# Brushed_Motor_MCU.net
KiCad netlist of a schematic drawn in Altium Designer
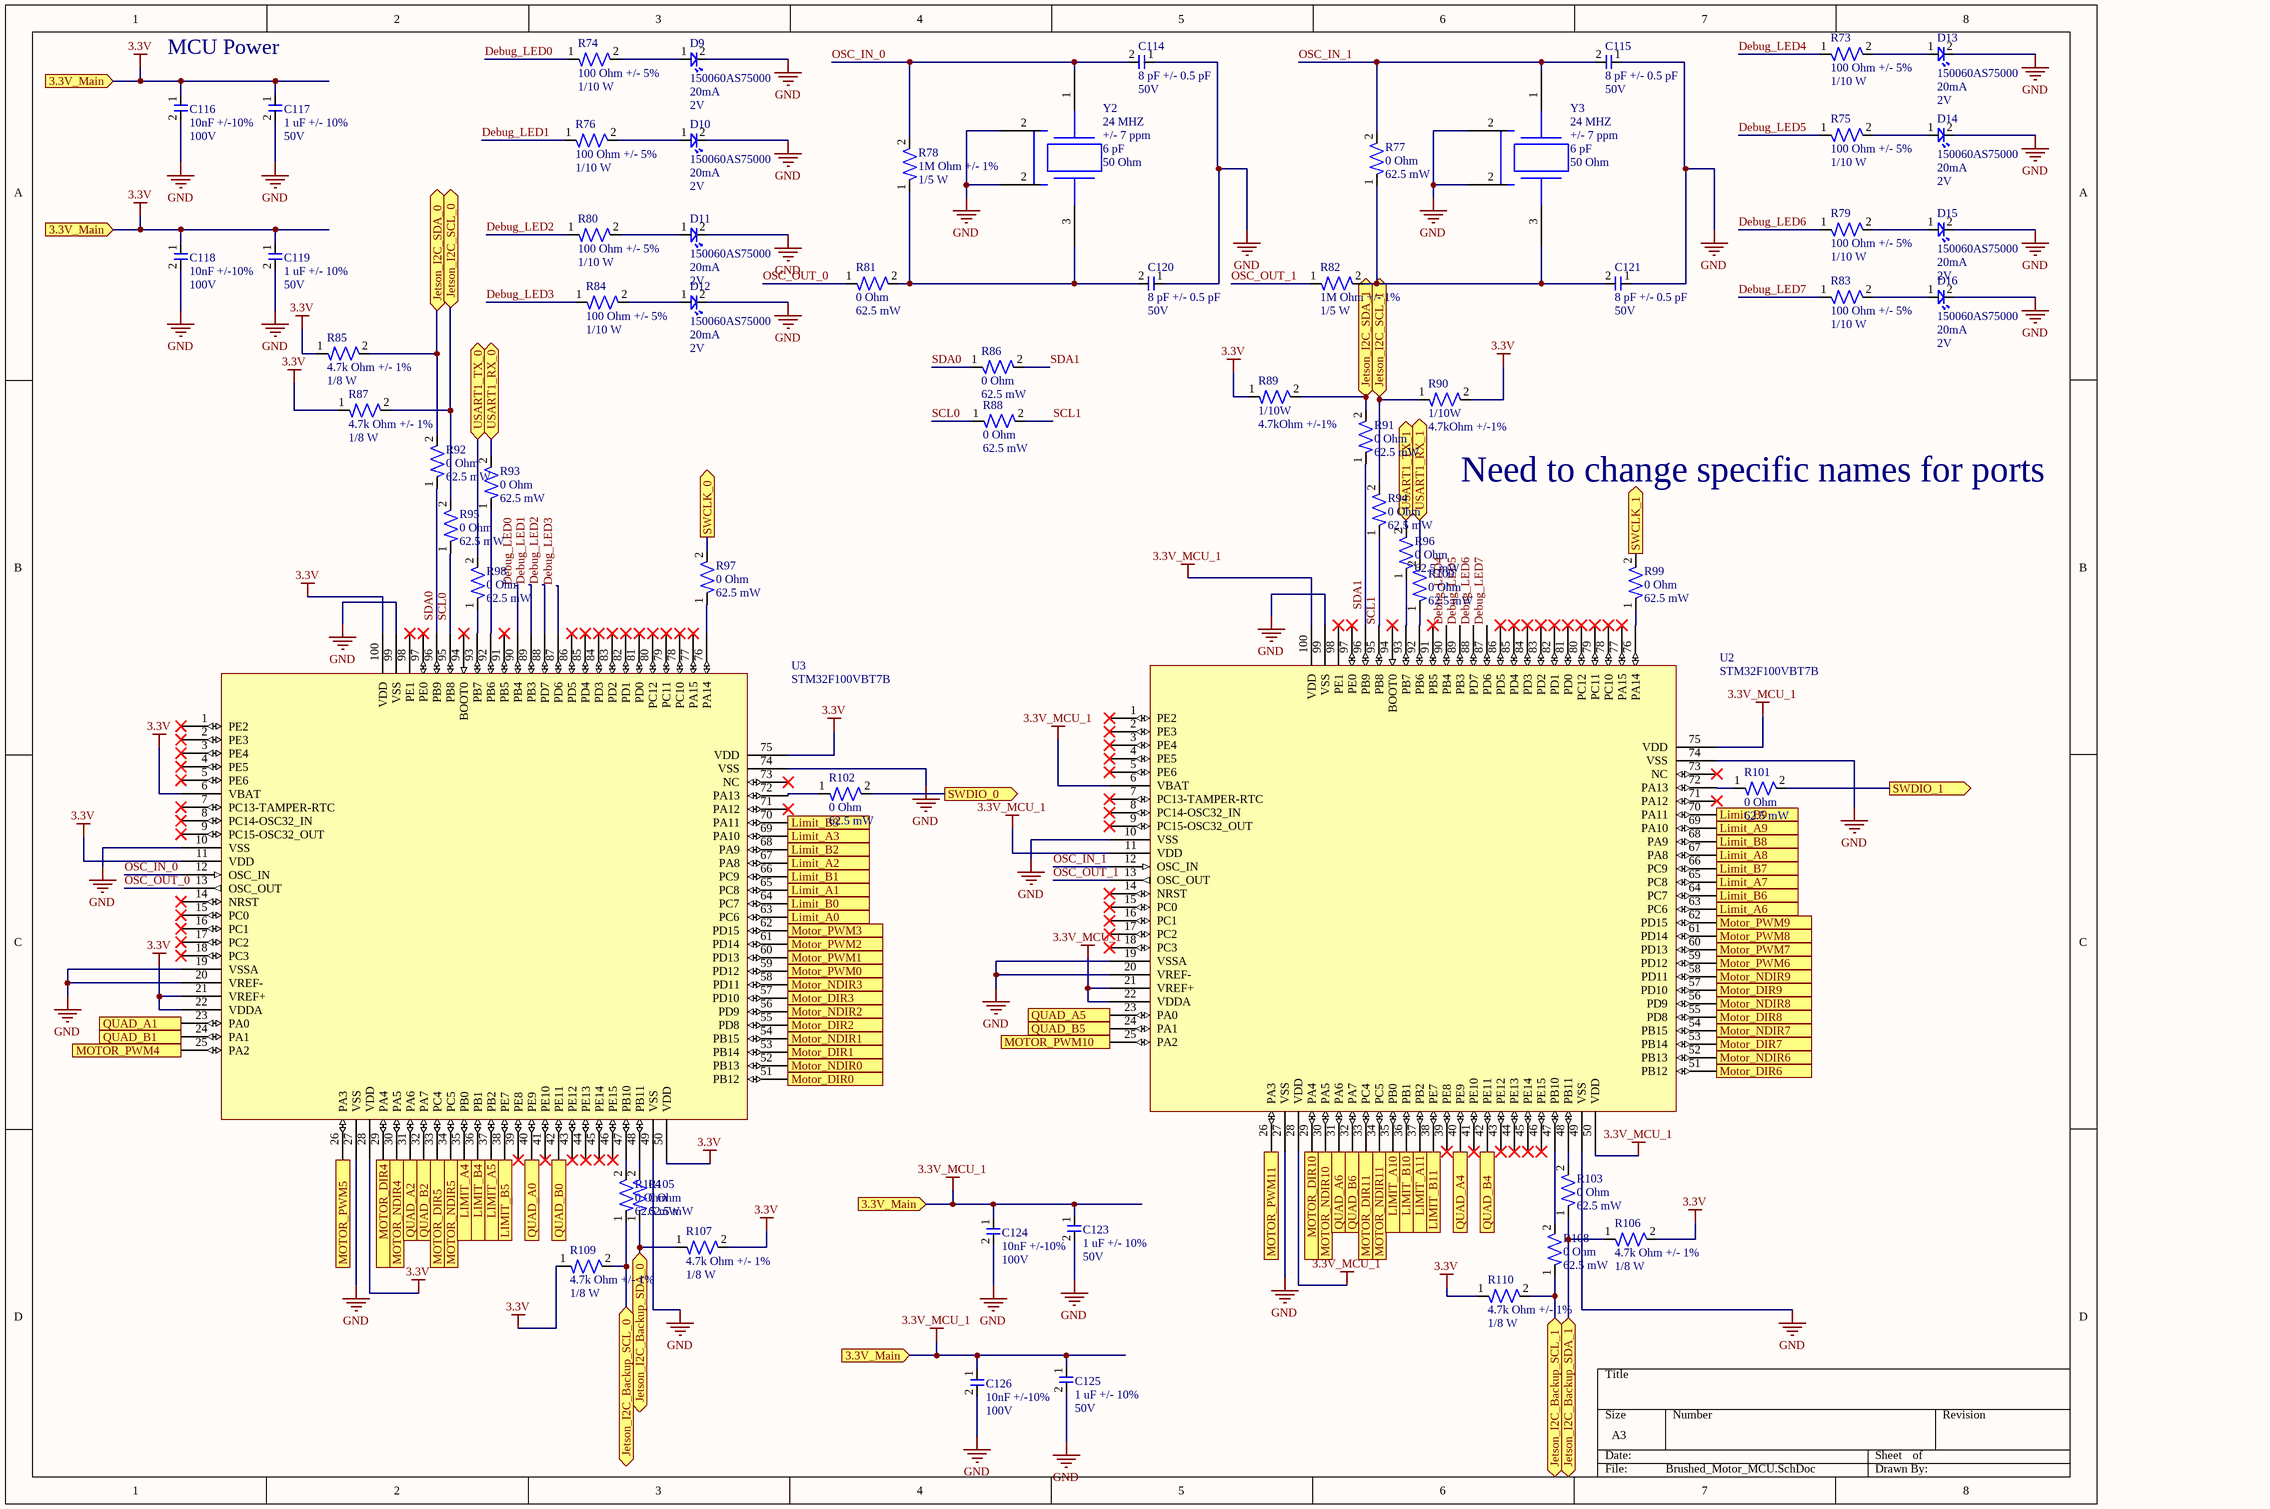
[diagram p0: Brushed_Motor_MCU.SchDoc]

(export (version "E")
  (design (tool "Eeschema 10.0.6"))
  (components
    (comp (ref "C114")
      (value "CC0402DRNPO9BN8R0")
      (footprint "CAP-0402")
      (description "50V 8pF NP0 ±0.5pF 0402 Multilayer Ceramic Capacitors MLCC - SMD/SMT ROHS")
      (fields
        (field (name "CAPAITANCE") "8 pF +/- 0.5 pF")
        (field (name "PARAMETER 2") "50V")
        (field (name "JLC PART NUMBER") "C327227")
      )
      (libsource (lib "MasterLib") (part "CAP-8P-0002-JLC"))
    )
    (comp (ref "C115")
      (value "CC0402DRNPO9BN8R0")
      (footprint "CAP-0402")
      (description "50V 8pF NP0 ±0.5pF 0402 Multilayer Ceramic Capacitors MLCC - SMD/SMT ROHS")
      (fields
        (field (name "CAPAITANCE") "8 pF +/- 0.5 pF")
        (field (name "PARAMETER 2") "50V")
        (field (name "JLC PART NUMBER") "C327227")
      )
      (libsource (lib "MasterLib") (part "CAP-8P-0002-JLC"))
    )
    (comp (ref "C116")
      (value "CC0603KRX7R0BB103")
      (footprint "CAP-0603")
      (description "100V 10nF X7R ±10% 0603 Multilayer Ceramic Capacitors MLCC - SMD/SMT ROHS")
      (fields
        (field (name "MANUFACTURER") "Yageo")
        (field (name "JLC PART NUMBER") "C107059")
        (field (name "CAPACITANCE") "10nF +/-10%")
        (field (name "VOLTAGE RATING") "100V")
      )
      (libsource (lib "MasterLib") (part "CAP-10N-0003-JLC"))
    )
    (comp (ref "C117")
      (value "GCM21BR71H105KA03L")
      (footprint "CAP-0805")
      (description "50V 1uF X7R ±10% 0805 Multilayer Ceramic Capacitors MLCC - SMD/SMT ROHS")
      (fields
        (field (name "JLC PART NUMBER") "C126592")
        (field (name "CAP") "1 uF +/- 10%")
        (field (name "VOLTAGE") "50V")
      )
      (libsource (lib "MasterLib") (part "CAP-1U-0003-JLC"))
    )
    (comp (ref "C118")
      (value "CC0603KRX7R0BB103")
      (footprint "CAP-0603")
      (description "100V 10nF X7R ±10% 0603 Multilayer Ceramic Capacitors MLCC - SMD/SMT ROHS")
      (fields
        (field (name "MANUFACTURER") "Yageo")
        (field (name "JLC PART NUMBER") "C107059")
        (field (name "CAPACITANCE") "10nF +/-10%")
        (field (name "VOLTAGE RATING") "100V")
      )
      (libsource (lib "MasterLib") (part "CAP-10N-0003-JLC"))
    )
    (comp (ref "C119")
      (value "GCM21BR71H105KA03L")
      (footprint "CAP-0805")
      (description "50V 1uF X7R ±10% 0805 Multilayer Ceramic Capacitors MLCC - SMD/SMT ROHS")
      (fields
        (field (name "JLC PART NUMBER") "C126592")
        (field (name "CAP") "1 uF +/- 10%")
        (field (name "VOLTAGE") "50V")
      )
      (libsource (lib "MasterLib") (part "CAP-1U-0003-JLC"))
    )
    (comp (ref "C120")
      (value "CC0402DRNPO9BN8R0")
      (footprint "CAP-0402")
      (description "50V 8pF NP0 ±0.5pF 0402 Multilayer Ceramic Capacitors MLCC - SMD/SMT ROHS")
      (fields
        (field (name "CAPAITANCE") "8 pF +/- 0.5 pF")
        (field (name "PARAMETER 2") "50V")
        (field (name "JLC PART NUMBER") "C327227")
      )
      (libsource (lib "MasterLib") (part "CAP-8P-0002-JLC"))
    )
    (comp (ref "C121")
      (value "CC0402DRNPO9BN8R0")
      (footprint "CAP-0402")
      (description "50V 8pF NP0 ±0.5pF 0402 Multilayer Ceramic Capacitors MLCC - SMD/SMT ROHS")
      (fields
        (field (name "CAPAITANCE") "8 pF +/- 0.5 pF")
        (field (name "PARAMETER 2") "50V")
        (field (name "JLC PART NUMBER") "C327227")
      )
      (libsource (lib "MasterLib") (part "CAP-8P-0002-JLC"))
    )
    (comp (ref "C123")
      (value "GCM21BR71H105KA03L")
      (footprint "CAP-0805")
      (description "50V 1uF X7R ±10% 0805 Multilayer Ceramic Capacitors MLCC - SMD/SMT ROHS")
      (fields
        (field (name "JLC PART NUMBER") "C126592")
        (field (name "CAP") "1 uF +/- 10%")
        (field (name "VOLTAGE") "50V")
      )
      (libsource (lib "MasterLib") (part "CAP-1U-0003-JLC"))
    )
    (comp (ref "C124")
      (value "CC0603KRX7R0BB103")
      (footprint "CAP-0603")
      (description "100V 10nF X7R ±10% 0603 Multilayer Ceramic Capacitors MLCC - SMD/SMT ROHS")
      (fields
        (field (name "MANUFACTURER") "Yageo")
        (field (name "JLC PART NUMBER") "C107059")
        (field (name "CAPACITANCE") "10nF +/-10%")
        (field (name "VOLTAGE RATING") "100V")
      )
      (libsource (lib "MasterLib") (part "CAP-10N-0003-JLC"))
    )
    (comp (ref "C125")
      (value "GCM21BR71H105KA03L")
      (footprint "CAP-0805")
      (description "50V 1uF X7R ±10% 0805 Multilayer Ceramic Capacitors MLCC - SMD/SMT ROHS")
      (fields
        (field (name "JLC PART NUMBER") "C126592")
        (field (name "CAP") "1 uF +/- 10%")
        (field (name "VOLTAGE") "50V")
      )
      (libsource (lib "MasterLib") (part "CAP-1U-0003-JLC"))
    )
    (comp (ref "C126")
      (value "CC0603KRX7R0BB103")
      (footprint "CAP-0603")
      (description "100V 10nF X7R ±10% 0603 Multilayer Ceramic Capacitors MLCC - SMD/SMT ROHS")
      (fields
        (field (name "MANUFACTURER") "Yageo")
        (field (name "JLC PART NUMBER") "C107059")
        (field (name "CAPACITANCE") "10nF +/-10%")
        (field (name "VOLTAGE RATING") "100V")
      )
      (libsource (lib "MasterLib") (part "CAP-10N-0003-JLC"))
    )
    (comp (ref "D9")
      (value "150060AS75000")
      (footprint "LED-0603")
      (description "CAP CER 0.1UF 100V X7R 0603")
      (fields
        (field (name "MANUFACTURER") "Wurth Electronik")
        (field (name "CURRENT RATING") "20mA")
        (field (name "VF") "2V")
      )
      (libsource (lib "MasterLib") (part "LED_Amber_0001"))
    )
    (comp (ref "D10")
      (value "150060AS75000")
      (footprint "LED-0603")
      (description "CAP CER 0.1UF 100V X7R 0603")
      (fields
        (field (name "MANUFACTURER") "Wurth Electronik")
        (field (name "CURRENT RATING") "20mA")
        (field (name "VF") "2V")
      )
      (libsource (lib "MasterLib") (part "LED_Amber_0001"))
    )
    (comp (ref "D11")
      (value "150060AS75000")
      (footprint "LED-0603")
      (description "CAP CER 0.1UF 100V X7R 0603")
      (fields
        (field (name "MANUFACTURER") "Wurth Electronik")
        (field (name "CURRENT RATING") "20mA")
        (field (name "VF") "2V")
      )
      (libsource (lib "MasterLib") (part "LED_Amber_0001"))
    )
    (comp (ref "D12")
      (value "150060AS75000")
      (footprint "LED-0603")
      (description "CAP CER 0.1UF 100V X7R 0603")
      (fields
        (field (name "MANUFACTURER") "Wurth Electronik")
        (field (name "CURRENT RATING") "20mA")
        (field (name "VF") "2V")
      )
      (libsource (lib "MasterLib") (part "LED_Amber_0001"))
    )
    (comp (ref "D13")
      (value "150060AS75000")
      (footprint "LED-0603")
      (description "CAP CER 0.1UF 100V X7R 0603")
      (fields
        (field (name "MANUFACTURER") "Wurth Electronik")
        (field (name "CURRENT RATING") "20mA")
        (field (name "VF") "2V")
      )
      (libsource (lib "MasterLib") (part "LED_Amber_0001"))
    )
    (comp (ref "D14")
      (value "150060AS75000")
      (footprint "LED-0603")
      (description "CAP CER 0.1UF 100V X7R 0603")
      (fields
        (field (name "MANUFACTURER") "Wurth Electronik")
        (field (name "CURRENT RATING") "20mA")
        (field (name "VF") "2V")
      )
      (libsource (lib "MasterLib") (part "LED_Amber_0001"))
    )
    (comp (ref "D15")
      (value "150060AS75000")
      (footprint "LED-0603")
      (description "CAP CER 0.1UF 100V X7R 0603")
      (fields
        (field (name "MANUFACTURER") "Wurth Electronik")
        (field (name "CURRENT RATING") "20mA")
        (field (name "VF") "2V")
      )
      (libsource (lib "MasterLib") (part "LED_Amber_0001"))
    )
    (comp (ref "D16")
      (value "150060AS75000")
      (footprint "LED-0603")
      (description "CAP CER 0.1UF 100V X7R 0603")
      (fields
        (field (name "MANUFACTURER") "Wurth Electronik")
        (field (name "CURRENT RATING") "20mA")
        (field (name "VF") "2V")
      )
      (libsource (lib "MasterLib") (part "LED_Amber_0001"))
    )
    (comp (ref "R73")
      (value "ERJ2GEJ101X")
      (footprint "RES-0402")
      (description "100mW Thick Film Resistors ±5% ±200ppm/℃ -55℃~+155℃ 100Ω 0402  Chip Resistor - Surface Mount ROHS")
      (fields
        (field (name "RESISTANCE") "100 Ohm +/- 5%")
        (field (name "POWER") "1/10 W")
        (field (name "JLC PART NUMBER") "C412972")
      )
      (libsource (lib "MasterLib") (part "RES-100-0003-JLC"))
    )
    (comp (ref "R74")
      (value "ERJ2GEJ101X")
      (footprint "RES-0402")
      (description "100mW Thick Film Resistors ±5% ±200ppm/℃ -55℃~+155℃ 100Ω 0402  Chip Resistor - Surface Mount ROHS")
      (fields
        (field (name "RESISTANCE") "100 Ohm +/- 5%")
        (field (name "POWER") "1/10 W")
        (field (name "JLC PART NUMBER") "C412972")
      )
      (libsource (lib "MasterLib") (part "RES-100-0003-JLC"))
    )
    (comp (ref "R75")
      (value "ERJ2GEJ101X")
      (footprint "RES-0402")
      (description "100mW Thick Film Resistors ±5% ±200ppm/℃ -55℃~+155℃ 100Ω 0402  Chip Resistor - Surface Mount ROHS")
      (fields
        (field (name "RESISTANCE") "100 Ohm +/- 5%")
        (field (name "POWER") "1/10 W")
        (field (name "JLC PART NUMBER") "C412972")
      )
      (libsource (lib "MasterLib") (part "RES-100-0003-JLC"))
    )
    (comp (ref "R76")
      (value "ERJ2GEJ101X")
      (footprint "RES-0402")
      (description "100mW Thick Film Resistors ±5% ±200ppm/℃ -55℃~+155℃ 100Ω 0402  Chip Resistor - Surface Mount ROHS")
      (fields
        (field (name "RESISTANCE") "100 Ohm +/- 5%")
        (field (name "POWER") "1/10 W")
        (field (name "JLC PART NUMBER") "C412972")
      )
      (libsource (lib "MasterLib") (part "RES-100-0003-JLC"))
    )
    (comp (ref "R77")
      (value "RC0402FR-070RL")
      (footprint "RES-0402")
      (description "62.5mW Thick Film Resistors 50V -55℃~+155℃ 0Ω 0402 Chip Resistor - Surface Mount ROHS")
      (fields
        (field (name "RESISTANCE") "0 Ohm")
        (field (name "POWER") "62.5 mW")
        (field (name "JLC PART NUMBER") "C106231")
      )
      (libsource (lib "MasterLib") (part "RES-0-0002-JLC"))
    )
    (comp (ref "R78")
      (value "ERJPA2F1004X")
      (footprint "RES-0402")
      (description "1/5W ±100ppm/℃ ±1% -55℃~+155℃ 1MΩ 0402 Chip Resistor - Surface Mount ROHS")
      (fields
        (field (name "RESISTANCE") "1M Ohm +/- 1%")
        (field (name "POWER") "1/5 W")
        (field (name "JLC PART NUMBER") "C427259")
      )
      (libsource (lib "MasterLib") (part "RES-1M-0002-JLC"))
    )
    (comp (ref "R79")
      (value "ERJ2GEJ101X")
      (footprint "RES-0402")
      (description "100mW Thick Film Resistors ±5% ±200ppm/℃ -55℃~+155℃ 100Ω 0402  Chip Resistor - Surface Mount ROHS")
      (fields
        (field (name "RESISTANCE") "100 Ohm +/- 5%")
        (field (name "POWER") "1/10 W")
        (field (name "JLC PART NUMBER") "C412972")
      )
      (libsource (lib "MasterLib") (part "RES-100-0003-JLC"))
    )
    (comp (ref "R80")
      (value "ERJ2GEJ101X")
      (footprint "RES-0402")
      (description "100mW Thick Film Resistors ±5% ±200ppm/℃ -55℃~+155℃ 100Ω 0402  Chip Resistor - Surface Mount ROHS")
      (fields
        (field (name "RESISTANCE") "100 Ohm +/- 5%")
        (field (name "POWER") "1/10 W")
        (field (name "JLC PART NUMBER") "C412972")
      )
      (libsource (lib "MasterLib") (part "RES-100-0003-JLC"))
    )
    (comp (ref "R81")
      (value "RC0402FR-070RL")
      (footprint "RES-0402")
      (description "62.5mW Thick Film Resistors 50V -55℃~+155℃ 0Ω 0402 Chip Resistor - Surface Mount ROHS")
      (fields
        (field (name "RESISTANCE") "0 Ohm")
        (field (name "POWER") "62.5 mW")
        (field (name "JLC PART NUMBER") "C106231")
      )
      (libsource (lib "MasterLib") (part "RES-0-0002-JLC"))
    )
    (comp (ref "R82")
      (value "ERJPA2F1004X")
      (footprint "RES-0402")
      (description "1/5W ±100ppm/℃ ±1% -55℃~+155℃ 1MΩ 0402 Chip Resistor - Surface Mount ROHS")
      (fields
        (field (name "RESISTANCE") "1M Ohm +/- 1%")
        (field (name "POWER") "1/5 W")
        (field (name "JLC PART NUMBER") "C427259")
      )
      (libsource (lib "MasterLib") (part "RES-1M-0002-JLC"))
    )
    (comp (ref "R83")
      (value "ERJ2GEJ101X")
      (footprint "RES-0402")
      (description "100mW Thick Film Resistors ±5% ±200ppm/℃ -55℃~+155℃ 100Ω 0402  Chip Resistor - Surface Mount ROHS")
      (fields
        (field (name "RESISTANCE") "100 Ohm +/- 5%")
        (field (name "POWER") "1/10 W")
        (field (name "JLC PART NUMBER") "C412972")
      )
      (libsource (lib "MasterLib") (part "RES-100-0003-JLC"))
    )
    (comp (ref "R84")
      (value "ERJ2GEJ101X")
      (footprint "RES-0402")
      (description "100mW Thick Film Resistors ±5% ±200ppm/℃ -55℃~+155℃ 100Ω 0402  Chip Resistor - Surface Mount ROHS")
      (fields
        (field (name "RESISTANCE") "100 Ohm +/- 5%")
        (field (name "POWER") "1/10 W")
        (field (name "JLC PART NUMBER") "C412972")
      )
      (libsource (lib "MasterLib") (part "RES-100-0003-JLC"))
    )
    (comp (ref "R85")
      (value "RC0402FR-7W4K7L")
      (footprint "RES-0402")
      (fields
        (field (name "RESISTANCE") "4.7k Ohm +/- 1%")
        (field (name "POWER") "1/8 W")
        (field (name "JLC PART NUMBER") "C606173")
      )
      (libsource (lib "MasterLib") (part "RES-4.7K-0003-JLC"))
    )
    (comp (ref "R86")
      (value "RC0402FR-070RL")
      (footprint "RES-0402")
      (description "62.5mW Thick Film Resistors 50V -55℃~+155℃ 0Ω 0402 Chip Resistor - Surface Mount ROHS")
      (fields
        (field (name "RESISTANCE") "0 Ohm")
        (field (name "POWER") "62.5 mW")
        (field (name "JLC PART NUMBER") "C106231")
      )
      (libsource (lib "MasterLib") (part "RES-0-0002-JLC"))
    )
    (comp (ref "R87")
      (value "RC0402FR-7W4K7L")
      (footprint "RES-0402")
      (fields
        (field (name "RESISTANCE") "4.7k Ohm +/- 1%")
        (field (name "POWER") "1/8 W")
        (field (name "JLC PART NUMBER") "C606173")
      )
      (libsource (lib "MasterLib") (part "RES-4.7K-0003-JLC"))
    )
    (comp (ref "R88")
      (value "RC0402FR-070RL")
      (footprint "RES-0402")
      (description "62.5mW Thick Film Resistors 50V -55℃~+155℃ 0Ω 0402 Chip Resistor - Surface Mount ROHS")
      (fields
        (field (name "RESISTANCE") "0 Ohm")
        (field (name "POWER") "62.5 mW")
        (field (name "JLC PART NUMBER") "C106231")
      )
      (libsource (lib "MasterLib") (part "RES-0-0002-JLC"))
    )
    (comp (ref "R89")
      (value "AF0603FR-074K7L")
      (footprint "RES-0603")
      (description "RES SMD 4.7K OHM 1% 1/10W 0603")
      (fields
        (field (name "MANUFACTURER") "YAGEO")
        (field (name "POWER RATING") "1/10W")
        (field (name "RESISTANCE") "4.7kOhm +/-1%")
      )
      (libsource (lib "MasterLib") (part "RES-4.7K-0002"))
    )
    (comp (ref "R90")
      (value "AF0603FR-074K7L")
      (footprint "RES-0603")
      (description "RES SMD 4.7K OHM 1% 1/10W 0603")
      (fields
        (field (name "MANUFACTURER") "YAGEO")
        (field (name "POWER RATING") "1/10W")
        (field (name "RESISTANCE") "4.7kOhm +/-1%")
      )
      (libsource (lib "MasterLib") (part "RES-4.7K-0002"))
    )
    (comp (ref "R91")
      (value "RC0402FR-070RL")
      (footprint "RES-0402")
      (description "62.5mW Thick Film Resistors 50V -55℃~+155℃ 0Ω 0402 Chip Resistor - Surface Mount ROHS")
      (fields
        (field (name "RESISTANCE") "0 Ohm")
        (field (name "POWER") "62.5 mW")
        (field (name "JLC PART NUMBER") "C106231")
      )
      (libsource (lib "MasterLib") (part "RES-0-0002-JLC"))
    )
    (comp (ref "R92")
      (value "RC0402FR-070RL")
      (footprint "RES-0402")
      (description "62.5mW Thick Film Resistors 50V -55℃~+155℃ 0Ω 0402 Chip Resistor - Surface Mount ROHS")
      (fields
        (field (name "RESISTANCE") "0 Ohm")
        (field (name "POWER") "62.5 mW")
        (field (name "JLC PART NUMBER") "C106231")
      )
      (libsource (lib "MasterLib") (part "RES-0-0002-JLC"))
    )
    (comp (ref "R93")
      (value "RC0402FR-070RL")
      (footprint "RES-0402")
      (description "62.5mW Thick Film Resistors 50V -55℃~+155℃ 0Ω 0402 Chip Resistor - Surface Mount ROHS")
      (fields
        (field (name "RESISTANCE") "0 Ohm")
        (field (name "POWER") "62.5 mW")
        (field (name "JLC PART NUMBER") "C106231")
      )
      (libsource (lib "MasterLib") (part "RES-0-0002-JLC"))
    )
    (comp (ref "R94")
      (value "RC0402FR-070RL")
      (footprint "RES-0402")
      (description "62.5mW Thick Film Resistors 50V -55℃~+155℃ 0Ω 0402 Chip Resistor - Surface Mount ROHS")
      (fields
        (field (name "RESISTANCE") "0 Ohm")
        (field (name "POWER") "62.5 mW")
        (field (name "JLC PART NUMBER") "C106231")
      )
      (libsource (lib "MasterLib") (part "RES-0-0002-JLC"))
    )
    (comp (ref "R95")
      (value "RC0402FR-070RL")
      (footprint "RES-0402")
      (description "62.5mW Thick Film Resistors 50V -55℃~+155℃ 0Ω 0402 Chip Resistor - Surface Mount ROHS")
      (fields
        (field (name "RESISTANCE") "0 Ohm")
        (field (name "POWER") "62.5 mW")
        (field (name "JLC PART NUMBER") "C106231")
      )
      (libsource (lib "MasterLib") (part "RES-0-0002-JLC"))
    )
    (comp (ref "R96")
      (value "RC0402FR-070RL")
      (footprint "RES-0402")
      (description "62.5mW Thick Film Resistors 50V -55℃~+155℃ 0Ω 0402 Chip Resistor - Surface Mount ROHS")
      (fields
        (field (name "RESISTANCE") "0 Ohm")
        (field (name "POWER") "62.5 mW")
        (field (name "JLC PART NUMBER") "C106231")
      )
      (libsource (lib "MasterLib") (part "RES-0-0002-JLC"))
    )
    (comp (ref "R97")
      (value "RC0402FR-070RL")
      (footprint "RES-0402")
      (description "62.5mW Thick Film Resistors 50V -55℃~+155℃ 0Ω 0402 Chip Resistor - Surface Mount ROHS")
      (fields
        (field (name "RESISTANCE") "0 Ohm")
        (field (name "POWER") "62.5 mW")
        (field (name "JLC PART NUMBER") "C106231")
      )
      (libsource (lib "MasterLib") (part "RES-0-0002-JLC"))
    )
    (comp (ref "R98")
      (value "RC0402FR-070RL")
      (footprint "RES-0402")
      (description "62.5mW Thick Film Resistors 50V -55℃~+155℃ 0Ω 0402 Chip Resistor - Surface Mount ROHS")
      (fields
        (field (name "RESISTANCE") "0 Ohm")
        (field (name "POWER") "62.5 mW")
        (field (name "JLC PART NUMBER") "C106231")
      )
      (libsource (lib "MasterLib") (part "RES-0-0002-JLC"))
    )
    (comp (ref "R99")
      (value "RC0402FR-070RL")
      (footprint "RES-0402")
      (description "62.5mW Thick Film Resistors 50V -55℃~+155℃ 0Ω 0402 Chip Resistor - Surface Mount ROHS")
      (fields
        (field (name "RESISTANCE") "0 Ohm")
        (field (name "POWER") "62.5 mW")
        (field (name "JLC PART NUMBER") "C106231")
      )
      (libsource (lib "MasterLib") (part "RES-0-0002-JLC"))
    )
    (comp (ref "R100")
      (value "RC0402FR-070RL")
      (footprint "RES-0402")
      (description "62.5mW Thick Film Resistors 50V -55℃~+155℃ 0Ω 0402 Chip Resistor - Surface Mount ROHS")
      (fields
        (field (name "RESISTANCE") "0 Ohm")
        (field (name "POWER") "62.5 mW")
        (field (name "JLC PART NUMBER") "C106231")
      )
      (libsource (lib "MasterLib") (part "RES-0-0002-JLC"))
    )
    (comp (ref "R101")
      (value "RC0402FR-070RL")
      (footprint "RES-0402")
      (description "62.5mW Thick Film Resistors 50V -55℃~+155℃ 0Ω 0402 Chip Resistor - Surface Mount ROHS")
      (fields
        (field (name "RESISTANCE") "0 Ohm")
        (field (name "POWER") "62.5 mW")
        (field (name "JLC PART NUMBER") "C106231")
      )
      (libsource (lib "MasterLib") (part "RES-0-0002-JLC"))
    )
    (comp (ref "R102")
      (value "RC0402FR-070RL")
      (footprint "RES-0402")
      (description "62.5mW Thick Film Resistors 50V -55℃~+155℃ 0Ω 0402 Chip Resistor - Surface Mount ROHS")
      (fields
        (field (name "RESISTANCE") "0 Ohm")
        (field (name "POWER") "62.5 mW")
        (field (name "JLC PART NUMBER") "C106231")
      )
      (libsource (lib "MasterLib") (part "RES-0-0002-JLC"))
    )
    (comp (ref "R103")
      (value "RC0402FR-070RL")
      (footprint "RES-0402")
      (description "62.5mW Thick Film Resistors 50V -55℃~+155℃ 0Ω 0402 Chip Resistor - Surface Mount ROHS")
      (fields
        (field (name "RESISTANCE") "0 Ohm")
        (field (name "POWER") "62.5 mW")
        (field (name "JLC PART NUMBER") "C106231")
      )
      (libsource (lib "MasterLib") (part "RES-0-0002-JLC"))
    )
    (comp (ref "R104")
      (value "RC0402FR-070RL")
      (footprint "RES-0402")
      (description "62.5mW Thick Film Resistors 50V -55℃~+155℃ 0Ω 0402 Chip Resistor - Surface Mount ROHS")
      (fields
        (field (name "RESISTANCE") "0 Ohm")
        (field (name "POWER") "62.5 mW")
        (field (name "JLC PART NUMBER") "C106231")
      )
      (libsource (lib "MasterLib") (part "RES-0-0002-JLC"))
    )
    (comp (ref "R105")
      (value "RC0402FR-070RL")
      (footprint "RES-0402")
      (description "62.5mW Thick Film Resistors 50V -55℃~+155℃ 0Ω 0402 Chip Resistor - Surface Mount ROHS")
      (fields
        (field (name "RESISTANCE") "0 Ohm")
        (field (name "POWER") "62.5 mW")
        (field (name "JLC PART NUMBER") "C106231")
      )
      (libsource (lib "MasterLib") (part "RES-0-0002-JLC"))
    )
    (comp (ref "R106")
      (value "RC0402FR-7W4K7L")
      (footprint "RES-0402")
      (fields
        (field (name "RESISTANCE") "4.7k Ohm +/- 1%")
        (field (name "POWER") "1/8 W")
        (field (name "JLC PART NUMBER") "C606173")
      )
      (libsource (lib "MasterLib") (part "RES-4.7K-0003-JLC"))
    )
    (comp (ref "R107")
      (value "RC0402FR-7W4K7L")
      (footprint "RES-0402")
      (fields
        (field (name "RESISTANCE") "4.7k Ohm +/- 1%")
        (field (name "POWER") "1/8 W")
        (field (name "JLC PART NUMBER") "C606173")
      )
      (libsource (lib "MasterLib") (part "RES-4.7K-0003-JLC"))
    )
    (comp (ref "R108")
      (value "RC0402FR-070RL")
      (footprint "RES-0402")
      (description "62.5mW Thick Film Resistors 50V -55℃~+155℃ 0Ω 0402 Chip Resistor - Surface Mount ROHS")
      (fields
        (field (name "RESISTANCE") "0 Ohm")
        (field (name "POWER") "62.5 mW")
        (field (name "JLC PART NUMBER") "C106231")
      )
      (libsource (lib "MasterLib") (part "RES-0-0002-JLC"))
    )
    (comp (ref "R109")
      (value "RC0402FR-7W4K7L")
      (footprint "RES-0402")
      (fields
        (field (name "RESISTANCE") "4.7k Ohm +/- 1%")
        (field (name "POWER") "1/8 W")
        (field (name "JLC PART NUMBER") "C606173")
      )
      (libsource (lib "MasterLib") (part "RES-4.7K-0003-JLC"))
    )
    (comp (ref "R110")
      (value "RC0402FR-7W4K7L")
      (footprint "RES-0402")
      (fields
        (field (name "RESISTANCE") "4.7k Ohm +/- 1%")
        (field (name "POWER") "1/8 W")
        (field (name "JLC PART NUMBER") "C606173")
      )
      (libsource (lib "MasterLib") (part "RES-4.7K-0003-JLC"))
    )
    (comp (ref "U2")
      (value "STM32F100VBT7B")
      (footprint "IC-STM32F100-0001")
      (libsource (lib "MasterLib") (part "IC-STM32F100-0001"))
    )
    (comp (ref "U3")
      (value "STM32F100VBT7B")
      (footprint "IC-STM32F100-0001")
      (libsource (lib "MasterLib") (part "IC-STM32F100-0001"))
    )
    (comp (ref "Y2")
      (value "ECS-240-6-37B-7KM-TR")
      (footprint "CRYSTAL-4-SMD-0001")
      (description "24 MHz ±7ppm Crystal 6pF 50 Ohms 4-SMD, No Lead")
      (fields
        (field (name "MANUFACTURER") "ECS Inc.")
        (field (name "FREQUENCY") "24 MHZ")
        (field (name "FREQUENCY TOLERANCE") "+/- 7 ppm")
        (field (name "LOAD CAPACITANCE") "6 pF")
        (field (name "EQUAVALENCE SERIES RESISTANCE") "50 Ohm")
      )
      (libsource (lib "MasterLib") (part "CRYSTAL-24MHz-0001"))
    )
    (comp (ref "Y3")
      (value "ECS-240-6-37B-7KM-TR")
      (footprint "CRYSTAL-4-SMD-0001")
      (description "24 MHz ±7ppm Crystal 6pF 50 Ohms 4-SMD, No Lead")
      (fields
        (field (name "MANUFACTURER") "ECS Inc.")
        (field (name "FREQUENCY") "24 MHZ")
        (field (name "FREQUENCY TOLERANCE") "+/- 7 ppm")
        (field (name "LOAD CAPACITANCE") "6 pF")
        (field (name "EQUAVALENCE SERIES RESISTANCE") "50 Ohm")
      )
      (libsource (lib "MasterLib") (part "CRYSTAL-24MHz-0001"))
    )
  )
  (nets
    (net (code "1") (name "/Debug_LED0") (class "Default")
      (node (ref "R74") (pin "1") (pinfunction "1_1") (pintype "passive"))
      (node (ref "U3") (pin "90") (pinfunction "PB4_90") (pintype "bidirectional"))
    )
    (net (code "2") (name "/Debug_LED1") (class "Default")
      (node (ref "R76") (pin "1") (pinfunction "1_1") (pintype "passive"))
      (node (ref "U3") (pin "89") (pinfunction "PB3_89") (pintype "bidirectional"))
    )
    (net (code "3") (name "/Debug_LED2") (class "Default")
      (node (ref "R80") (pin "1") (pinfunction "1_1") (pintype "passive"))
      (node (ref "U3") (pin "88") (pinfunction "PD7_88") (pintype "bidirectional"))
    )
    (net (code "4") (name "/Debug_LED3") (class "Default")
      (node (ref "R84") (pin "1") (pinfunction "1_1") (pintype "passive"))
      (node (ref "U3") (pin "87") (pinfunction "PD6_87") (pintype "bidirectional"))
    )
    (net (code "5") (name "/Debug_LED4") (class "Default")
      (node (ref "R73") (pin "1") (pinfunction "1_1") (pintype "passive"))
      (node (ref "U2") (pin "90") (pinfunction "PB4_90") (pintype "bidirectional"))
    )
    (net (code "6") (name "/Debug_LED5") (class "Default")
      (node (ref "R75") (pin "1") (pinfunction "1_1") (pintype "passive"))
      (node (ref "U2") (pin "89") (pinfunction "PB3_89") (pintype "bidirectional"))
    )
    (net (code "7") (name "/Debug_LED6") (class "Default")
      (node (ref "R79") (pin "1") (pinfunction "1_1") (pintype "passive"))
      (node (ref "U2") (pin "88") (pinfunction "PD7_88") (pintype "bidirectional"))
    )
    (net (code "8") (name "/Debug_LED7") (class "Default")
      (node (ref "R83") (pin "1") (pinfunction "1_1") (pintype "passive"))
      (node (ref "U2") (pin "87") (pinfunction "PD6_87") (pintype "bidirectional"))
    )
    (net (code "9") (name "/Jetson_I2C_Backup_SCL_0") (class "Default")
      (node (ref "R104") (pin "1") (pinfunction "1_1") (pintype "passive"))
      (node (ref "R109") (pin "2") (pinfunction "2_2") (pintype "passive"))
    )
    (net (code "10") (name "/Jetson_I2C_Backup_SCL_1") (class "Default")
      (node (ref "R108") (pin "1") (pinfunction "1_1") (pintype "passive"))
      (node (ref "R110") (pin "2") (pinfunction "2_2") (pintype "passive"))
    )
    (net (code "11") (name "/Jetson_I2C_Backup_SDA_0") (class "Default")
      (node (ref "R105") (pin "1") (pinfunction "1_1") (pintype "passive"))
      (node (ref "R107") (pin "1") (pinfunction "1_1") (pintype "passive"))
    )
    (net (code "12") (name "/Jetson_I2C_Backup_SDA_1") (class "Default")
      (node (ref "R103") (pin "1") (pinfunction "1_1") (pintype "passive"))
      (node (ref "R106") (pin "1") (pinfunction "1_1") (pintype "passive"))
    )
    (net (code "13") (name "/Jetson_I2C_SCL_0") (class "Default")
      (node (ref "R87") (pin "2") (pinfunction "2_2") (pintype "passive"))
      (node (ref "R95") (pin "2") (pinfunction "2_2") (pintype "passive"))
    )
    (net (code "14") (name "/Jetson_I2C_SCL_1") (class "Default")
      (node (ref "R90") (pin "1") (pinfunction "1_1") (pintype "passive"))
      (node (ref "R94") (pin "2") (pinfunction "2_2") (pintype "passive"))
    )
    (net (code "15") (name "/Jetson_I2C_SDA_0") (class "Default")
      (node (ref "R85") (pin "2") (pinfunction "2_2") (pintype "passive"))
      (node (ref "R92") (pin "2") (pinfunction "2_2") (pintype "passive"))
    )
    (net (code "16") (name "/Jetson_I2C_SDA_1") (class "Default")
      (node (ref "R89") (pin "2") (pinfunction "2_2") (pintype "passive"))
      (node (ref "R91") (pin "2") (pinfunction "2_2") (pintype "passive"))
    )
    (net (code "17") (name "/LIMIT_A4") (class "Default")
      (node (ref "U3") (pin "35") (pinfunction "PB0_35") (pintype "bidirectional"))
    )
    (net (code "18") (name "/LIMIT_A5") (class "Default")
      (node (ref "U3") (pin "37") (pinfunction "PB2_37") (pintype "bidirectional"))
    )
    (net (code "19") (name "/LIMIT_A10") (class "Default")
      (node (ref "U2") (pin "35") (pinfunction "PB0_35") (pintype "bidirectional"))
    )
    (net (code "20") (name "/LIMIT_A11") (class "Default")
      (node (ref "U2") (pin "37") (pinfunction "PB2_37") (pintype "bidirectional"))
    )
    (net (code "21") (name "/LIMIT_B4") (class "Default")
      (node (ref "U3") (pin "36") (pinfunction "PB1_36") (pintype "bidirectional"))
    )
    (net (code "22") (name "/LIMIT_B5") (class "Default")
      (node (ref "U3") (pin "38") (pinfunction "PE7_38") (pintype "bidirectional"))
    )
    (net (code "23") (name "/LIMIT_B10") (class "Default")
      (node (ref "U2") (pin "36") (pinfunction "PB1_36") (pintype "bidirectional"))
    )
    (net (code "24") (name "/LIMIT_B11") (class "Default")
      (node (ref "U2") (pin "38") (pinfunction "PE7_38") (pintype "bidirectional"))
    )
    (net (code "25") (name "/Limit_A0") (class "Default")
      (node (ref "U3") (pin "63") (pinfunction "PC6_63") (pintype "bidirectional"))
    )
    (net (code "26") (name "/Limit_A1") (class "Default")
      (node (ref "U3") (pin "65") (pinfunction "PC8_65") (pintype "bidirectional"))
    )
    (net (code "27") (name "/Limit_A2") (class "Default")
      (node (ref "U3") (pin "67") (pinfunction "PA8_67") (pintype "bidirectional"))
    )
    (net (code "28") (name "/Limit_A3") (class "Default")
      (node (ref "U3") (pin "69") (pinfunction "PA10_69") (pintype "bidirectional"))
    )
    (net (code "29") (name "/Limit_A6") (class "Default")
      (node (ref "U2") (pin "63") (pinfunction "PC6_63") (pintype "bidirectional"))
    )
    (net (code "30") (name "/Limit_A7") (class "Default")
      (node (ref "U2") (pin "65") (pinfunction "PC8_65") (pintype "bidirectional"))
    )
    (net (code "31") (name "/Limit_A8") (class "Default")
      (node (ref "U2") (pin "67") (pinfunction "PA8_67") (pintype "bidirectional"))
    )
    (net (code "32") (name "/Limit_A9") (class "Default")
      (node (ref "U2") (pin "69") (pinfunction "PA10_69") (pintype "bidirectional"))
    )
    (net (code "33") (name "/Limit_B0") (class "Default")
      (node (ref "U3") (pin "64") (pinfunction "PC7_64") (pintype "bidirectional"))
    )
    (net (code "34") (name "/Limit_B1") (class "Default")
      (node (ref "U3") (pin "66") (pinfunction "PC9_66") (pintype "bidirectional"))
    )
    (net (code "35") (name "/Limit_B2") (class "Default")
      (node (ref "U3") (pin "68") (pinfunction "PA9_68") (pintype "bidirectional"))
    )
    (net (code "36") (name "/Limit_B3") (class "Default")
      (node (ref "U3") (pin "70") (pinfunction "PA11_70") (pintype "bidirectional"))
    )
    (net (code "37") (name "/Limit_B6") (class "Default")
      (node (ref "U2") (pin "64") (pinfunction "PC7_64") (pintype "bidirectional"))
    )
    (net (code "38") (name "/Limit_B7") (class "Default")
      (node (ref "U2") (pin "66") (pinfunction "PC9_66") (pintype "bidirectional"))
    )
    (net (code "39") (name "/Limit_B8") (class "Default")
      (node (ref "U2") (pin "68") (pinfunction "PA9_68") (pintype "bidirectional"))
    )
    (net (code "40") (name "/Limit_B9") (class "Default")
      (node (ref "U2") (pin "70") (pinfunction "PA11_70") (pintype "bidirectional"))
    )
    (net (code "41") (name "/MOTOR_DIR4") (class "Default")
      (node (ref "U3") (pin "29") (pinfunction "PA4_29") (pintype "bidirectional"))
    )
    (net (code "42") (name "/MOTOR_DIR5") (class "Default")
      (node (ref "U3") (pin "33") (pinfunction "PC4_33") (pintype "bidirectional"))
    )
    (net (code "43") (name "/MOTOR_DIR10") (class "Default")
      (node (ref "U2") (pin "29") (pinfunction "PA4_29") (pintype "bidirectional"))
    )
    (net (code "44") (name "/MOTOR_DIR11") (class "Default")
      (node (ref "U2") (pin "33") (pinfunction "PC4_33") (pintype "bidirectional"))
    )
    (net (code "45") (name "/MOTOR_NDIR4") (class "Default")
      (node (ref "U3") (pin "30") (pinfunction "PA5_30") (pintype "bidirectional"))
    )
    (net (code "46") (name "/MOTOR_NDIR5") (class "Default")
      (node (ref "U3") (pin "34") (pinfunction "PC5_34") (pintype "bidirectional"))
    )
    (net (code "47") (name "/MOTOR_NDIR10") (class "Default")
      (node (ref "U2") (pin "30") (pinfunction "PA5_30") (pintype "bidirectional"))
    )
    (net (code "48") (name "/MOTOR_NDIR11") (class "Default")
      (node (ref "U2") (pin "34") (pinfunction "PC5_34") (pintype "bidirectional"))
    )
    (net (code "49") (name "/MOTOR_PWM4") (class "Default")
      (node (ref "U3") (pin "25") (pinfunction "PA2_25") (pintype "bidirectional"))
    )
    (net (code "50") (name "/MOTOR_PWM5") (class "Default")
      (node (ref "U3") (pin "26") (pinfunction "PA3_26") (pintype "bidirectional"))
    )
    (net (code "51") (name "/MOTOR_PWM10") (class "Default")
      (node (ref "U2") (pin "25") (pinfunction "PA2_25") (pintype "bidirectional"))
    )
    (net (code "52") (name "/MOTOR_PWM11") (class "Default")
      (node (ref "U2") (pin "26") (pinfunction "PA3_26") (pintype "bidirectional"))
    )
    (net (code "53") (name "/Motor_DIR0") (class "Default")
      (node (ref "U3") (pin "51") (pinfunction "PB12_51") (pintype "bidirectional"))
    )
    (net (code "54") (name "/Motor_DIR1") (class "Default")
      (node (ref "U3") (pin "53") (pinfunction "PB14_53") (pintype "bidirectional"))
    )
    (net (code "55") (name "/Motor_DIR2") (class "Default")
      (node (ref "U3") (pin "55") (pinfunction "PD8_55") (pintype "bidirectional"))
    )
    (net (code "56") (name "/Motor_DIR3") (class "Default")
      (node (ref "U3") (pin "57") (pinfunction "PD10_57") (pintype "bidirectional"))
    )
    (net (code "57") (name "/Motor_DIR6") (class "Default")
      (node (ref "U2") (pin "51") (pinfunction "PB12_51") (pintype "bidirectional"))
    )
    (net (code "58") (name "/Motor_DIR7") (class "Default")
      (node (ref "U2") (pin "53") (pinfunction "PB14_53") (pintype "bidirectional"))
    )
    (net (code "59") (name "/Motor_DIR8") (class "Default")
      (node (ref "U2") (pin "55") (pinfunction "PD8_55") (pintype "bidirectional"))
    )
    (net (code "60") (name "/Motor_DIR9") (class "Default")
      (node (ref "U2") (pin "57") (pinfunction "PD10_57") (pintype "bidirectional"))
    )
    (net (code "61") (name "/Motor_NDIR0") (class "Default")
      (node (ref "U3") (pin "52") (pinfunction "PB13_52") (pintype "bidirectional"))
    )
    (net (code "62") (name "/Motor_NDIR1") (class "Default")
      (node (ref "U3") (pin "54") (pinfunction "PB15_54") (pintype "bidirectional"))
    )
    (net (code "63") (name "/Motor_NDIR2") (class "Default")
      (node (ref "U3") (pin "56") (pinfunction "PD9_56") (pintype "bidirectional"))
    )
    (net (code "64") (name "/Motor_NDIR3") (class "Default")
      (node (ref "U3") (pin "58") (pinfunction "PD11_58") (pintype "bidirectional"))
    )
    (net (code "65") (name "/Motor_NDIR6") (class "Default")
      (node (ref "U2") (pin "52") (pinfunction "PB13_52") (pintype "bidirectional"))
    )
    (net (code "66") (name "/Motor_NDIR7") (class "Default")
      (node (ref "U2") (pin "54") (pinfunction "PB15_54") (pintype "bidirectional"))
    )
    (net (code "67") (name "/Motor_NDIR8") (class "Default")
      (node (ref "U2") (pin "56") (pinfunction "PD9_56") (pintype "bidirectional"))
    )
    (net (code "68") (name "/Motor_NDIR9") (class "Default")
      (node (ref "U2") (pin "58") (pinfunction "PD11_58") (pintype "bidirectional"))
    )
    (net (code "69") (name "/Motor_PWM0") (class "Default")
      (node (ref "U3") (pin "59") (pinfunction "PD12_59") (pintype "bidirectional"))
    )
    (net (code "70") (name "/Motor_PWM1") (class "Default")
      (node (ref "U3") (pin "60") (pinfunction "PD13_60") (pintype "bidirectional"))
    )
    (net (code "71") (name "/Motor_PWM2") (class "Default")
      (node (ref "U3") (pin "61") (pinfunction "PD14_61") (pintype "bidirectional"))
    )
    (net (code "72") (name "/Motor_PWM3") (class "Default")
      (node (ref "U3") (pin "62") (pinfunction "PD15_62") (pintype "bidirectional"))
    )
    (net (code "73") (name "/Motor_PWM6") (class "Default")
      (node (ref "U2") (pin "59") (pinfunction "PD12_59") (pintype "bidirectional"))
    )
    (net (code "74") (name "/Motor_PWM7") (class "Default")
      (node (ref "U2") (pin "60") (pinfunction "PD13_60") (pintype "bidirectional"))
    )
    (net (code "75") (name "/Motor_PWM8") (class "Default")
      (node (ref "U2") (pin "61") (pinfunction "PD14_61") (pintype "bidirectional"))
    )
    (net (code "76") (name "/Motor_PWM9") (class "Default")
      (node (ref "U2") (pin "62") (pinfunction "PD15_62") (pintype "bidirectional"))
    )
    (net (code "77") (name "/OSC_IN_0") (class "Default")
      (node (ref "C114") (pin "2") (pinfunction "2_2") (pintype "passive"))
      (node (ref "R78") (pin "2") (pinfunction "2_2") (pintype "passive"))
      (node (ref "U3") (pin "12") (pinfunction "OSC_IN_12") (pintype "input"))
      (node (ref "Y2") (pin "1") (pinfunction "1_1") (pintype "passive"))
    )
    (net (code "78") (name "/OSC_IN_1") (class "Default")
      (node (ref "C115") (pin "2") (pinfunction "2_2") (pintype "passive"))
      (node (ref "R77") (pin "2") (pinfunction "2_2") (pintype "passive"))
      (node (ref "U2") (pin "12") (pinfunction "OSC_IN_12") (pintype "input"))
      (node (ref "Y3") (pin "1") (pinfunction "1_1") (pintype "passive"))
    )
    (net (code "79") (name "/OSC_OUT_0") (class "Default")
      (node (ref "R81") (pin "1") (pinfunction "1_1") (pintype "passive"))
      (node (ref "U3") (pin "13") (pinfunction "OSC_OUT_13") (pintype "output"))
    )
    (net (code "80") (name "/OSC_OUT_1") (class "Default")
      (node (ref "R82") (pin "1") (pinfunction "1_1") (pintype "passive"))
      (node (ref "U2") (pin "13") (pinfunction "OSC_OUT_13") (pintype "output"))
    )
    (net (code "81") (name "/QUAD_A0") (class "Default")
      (node (ref "U3") (pin "40") (pinfunction "PE9_40") (pintype "bidirectional"))
    )
    (net (code "82") (name "/QUAD_A1") (class "Default")
      (node (ref "U3") (pin "23") (pinfunction "PA0_23") (pintype "bidirectional"))
    )
    (net (code "83") (name "/QUAD_A2") (class "Default")
      (node (ref "U3") (pin "31") (pinfunction "PA6_31") (pintype "bidirectional"))
    )
    (net (code "84") (name "/QUAD_A4") (class "Default")
      (node (ref "U2") (pin "40") (pinfunction "PE9_40") (pintype "bidirectional"))
    )
    (net (code "85") (name "/QUAD_A5") (class "Default")
      (node (ref "U2") (pin "23") (pinfunction "PA0_23") (pintype "bidirectional"))
    )
    (net (code "86") (name "/QUAD_A6") (class "Default")
      (node (ref "U2") (pin "31") (pinfunction "PA6_31") (pintype "bidirectional"))
    )
    (net (code "87") (name "/QUAD_B0") (class "Default")
      (node (ref "U3") (pin "42") (pinfunction "PE11_42") (pintype "bidirectional"))
    )
    (net (code "88") (name "/QUAD_B1") (class "Default")
      (node (ref "U3") (pin "24") (pinfunction "PA1_24") (pintype "bidirectional"))
    )
    (net (code "89") (name "/QUAD_B2") (class "Default")
      (node (ref "U3") (pin "32") (pinfunction "PA7_32") (pintype "bidirectional"))
    )
    (net (code "90") (name "/QUAD_B4") (class "Default")
      (node (ref "U2") (pin "42") (pinfunction "PE11_42") (pintype "bidirectional"))
    )
    (net (code "91") (name "/QUAD_B5") (class "Default")
      (node (ref "U2") (pin "24") (pinfunction "PA1_24") (pintype "bidirectional"))
    )
    (net (code "92") (name "/QUAD_B6") (class "Default")
      (node (ref "U2") (pin "32") (pinfunction "PA7_32") (pintype "bidirectional"))
    )
    (net (code "93") (name "/SCL0") (class "Default")
      (node (ref "R88") (pin "1") (pinfunction "1_1") (pintype "passive"))
      (node (ref "R95") (pin "1") (pinfunction "1_1") (pintype "passive"))
      (node (ref "U3") (pin "95") (pinfunction "PB8_95") (pintype "bidirectional"))
    )
    (net (code "94") (name "/SCL1") (class "Default")
      (node (ref "R88") (pin "2") (pinfunction "2_2") (pintype "passive"))
      (node (ref "R94") (pin "1") (pinfunction "1_1") (pintype "passive"))
      (node (ref "U2") (pin "95") (pinfunction "PB8_95") (pintype "bidirectional"))
    )
    (net (code "95") (name "/SDA0") (class "Default")
      (node (ref "R86") (pin "1") (pinfunction "1_1") (pintype "passive"))
      (node (ref "R92") (pin "1") (pinfunction "1_1") (pintype "passive"))
      (node (ref "U3") (pin "96") (pinfunction "PB9_96") (pintype "bidirectional"))
    )
    (net (code "96") (name "/SDA1") (class "Default")
      (node (ref "R86") (pin "2") (pinfunction "2_2") (pintype "passive"))
      (node (ref "R91") (pin "1") (pinfunction "1_1") (pintype "passive"))
      (node (ref "U2") (pin "96") (pinfunction "PB9_96") (pintype "bidirectional"))
    )
    (net (code "97") (name "/SWCLK_0") (class "Default")
      (node (ref "R97") (pin "2") (pinfunction "2_2") (pintype "passive"))
    )
    (net (code "98") (name "/SWCLK_1") (class "Default")
      (node (ref "R99") (pin "2") (pinfunction "2_2") (pintype "passive"))
    )
    (net (code "99") (name "/SWDIO_0") (class "Default")
      (node (ref "R102") (pin "2") (pinfunction "2_2") (pintype "passive"))
    )
    (net (code "100") (name "/SWDIO_1") (class "Default")
      (node (ref "R101") (pin "2") (pinfunction "2_2") (pintype "passive"))
    )
    (net (code "101") (name "/USART1_RX_0") (class "Default")
      (node (ref "R93") (pin "2") (pinfunction "2_2") (pintype "passive"))
    )
    (net (code "102") (name "/USART1_RX_1") (class "Default")
      (node (ref "R100") (pin "2") (pinfunction "2_2") (pintype "passive"))
    )
    (net (code "103") (name "/USART1_TX_0") (class "Default")
      (node (ref "R98") (pin "2") (pinfunction "2_2") (pintype "passive"))
    )
    (net (code "104") (name "/USART1_TX_1") (class "Default")
      (node (ref "R96") (pin "2") (pinfunction "2_2") (pintype "passive"))
    )
    (net (code "105") (name "3.3V") (class "Default")
      (node (ref "C116") (pin "1") (pinfunction "1_1") (pintype "passive"))
      (node (ref "C117") (pin "1") (pinfunction "1_1") (pintype "passive"))
      (node (ref "C118") (pin "1") (pinfunction "1_1") (pintype "passive"))
      (node (ref "C119") (pin "1") (pinfunction "1_1") (pintype "passive"))
      (node (ref "C123") (pin "1") (pinfunction "1_1") (pintype "passive"))
      (node (ref "C124") (pin "1") (pinfunction "1_1") (pintype "passive"))
      (node (ref "C125") (pin "1") (pinfunction "1_1") (pintype "passive"))
      (node (ref "C126") (pin "1") (pinfunction "1_1") (pintype "passive"))
      (node (ref "R106") (pin "2") (pinfunction "2_2") (pintype "passive"))
      (node (ref "R107") (pin "2") (pinfunction "2_2") (pintype "passive"))
      (node (ref "R109") (pin "1") (pinfunction "1_1") (pintype "passive"))
      (node (ref "R110") (pin "1") (pinfunction "1_1") (pintype "passive"))
      (node (ref "R85") (pin "1") (pinfunction "1_1") (pintype "passive"))
      (node (ref "R87") (pin "1") (pinfunction "1_1") (pintype "passive"))
      (node (ref "R89") (pin "1") (pinfunction "1_1") (pintype "passive"))
      (node (ref "R90") (pin "2") (pinfunction "2_2") (pintype "passive"))
      (node (ref "U2") (pin "100") (pinfunction "VDD_100") (pintype "power_in"))
      (node (ref "U2") (pin "11") (pinfunction "VDD_11") (pintype "power_in"))
      (node (ref "U2") (pin "21") (pinfunction "VREF+_21") (pintype "power_in"))
      (node (ref "U2") (pin "22") (pinfunction "VDDA_22") (pintype "power_in"))
      (node (ref "U2") (pin "28") (pinfunction "VDD_28") (pintype "power_in"))
      (node (ref "U2") (pin "50") (pinfunction "VDD_50") (pintype "power_in"))
      (node (ref "U2") (pin "6") (pinfunction "VBAT_6") (pintype "power_in"))
      (node (ref "U2") (pin "75") (pinfunction "VDD_75") (pintype "power_in"))
      (node (ref "U3") (pin "100") (pinfunction "VDD_100") (pintype "power_in"))
      (node (ref "U3") (pin "11") (pinfunction "VDD_11") (pintype "power_in"))
      (node (ref "U3") (pin "21") (pinfunction "VREF+_21") (pintype "power_in"))
      (node (ref "U3") (pin "22") (pinfunction "VDDA_22") (pintype "power_in"))
      (node (ref "U3") (pin "28") (pinfunction "VDD_28") (pintype "power_in"))
      (node (ref "U3") (pin "50") (pinfunction "VDD_50") (pintype "power_in"))
      (node (ref "U3") (pin "6") (pinfunction "VBAT_6") (pintype "power_in"))
      (node (ref "U3") (pin "75") (pinfunction "VDD_75") (pintype "power_in"))
    )
    (net (code "106") (name "GND") (class "Default")
      (node (ref "C114") (pin "1") (pinfunction "1_1") (pintype "passive"))
      (node (ref "C115") (pin "1") (pinfunction "1_1") (pintype "passive"))
      (node (ref "C116") (pin "2") (pinfunction "2_2") (pintype "passive"))
      (node (ref "C117") (pin "2") (pinfunction "2_2") (pintype "passive"))
      (node (ref "C118") (pin "2") (pinfunction "2_2") (pintype "passive"))
      (node (ref "C119") (pin "2") (pinfunction "2_2") (pintype "passive"))
      (node (ref "C120") (pin "1") (pinfunction "1_1") (pintype "passive"))
      (node (ref "C121") (pin "1") (pinfunction "1_1") (pintype "passive"))
      (node (ref "C123") (pin "2") (pinfunction "2_2") (pintype "passive"))
      (node (ref "C124") (pin "2") (pinfunction "2_2") (pintype "passive"))
      (node (ref "C125") (pin "2") (pinfunction "2_2") (pintype "passive"))
      (node (ref "C126") (pin "2") (pinfunction "2_2") (pintype "passive"))
      (node (ref "D10") (pin "2") (pinfunction "2_2") (pintype "passive"))
      (node (ref "D11") (pin "2") (pinfunction "2_2") (pintype "passive"))
      (node (ref "D12") (pin "2") (pinfunction "2_2") (pintype "passive"))
      (node (ref "D13") (pin "2") (pinfunction "2_2") (pintype "passive"))
      (node (ref "D14") (pin "2") (pinfunction "2_2") (pintype "passive"))
      (node (ref "D15") (pin "2") (pinfunction "2_2") (pintype "passive"))
      (node (ref "D16") (pin "2") (pinfunction "2_2") (pintype "passive"))
      (node (ref "D9") (pin "2") (pinfunction "2_2") (pintype "passive"))
      (node (ref "U2") (pin "10") (pinfunction "VSS_10") (pintype "power_in"))
      (node (ref "U2") (pin "19") (pinfunction "VSSA_19") (pintype "power_in"))
      (node (ref "U2") (pin "20") (pinfunction "VREF-_20") (pintype "power_in"))
      (node (ref "U2") (pin "27") (pinfunction "VSS_27") (pintype "power_in"))
      (node (ref "U2") (pin "49") (pinfunction "VSS_49") (pintype "power_in"))
      (node (ref "U2") (pin "74") (pinfunction "VSS_74") (pintype "power_in"))
      (node (ref "U2") (pin "99") (pinfunction "VSS_99") (pintype "power_in"))
      (node (ref "U3") (pin "10") (pinfunction "VSS_10") (pintype "power_in"))
      (node (ref "U3") (pin "19") (pinfunction "VSSA_19") (pintype "power_in"))
      (node (ref "U3") (pin "20") (pinfunction "VREF-_20") (pintype "power_in"))
      (node (ref "U3") (pin "27") (pinfunction "VSS_27") (pintype "power_in"))
      (node (ref "U3") (pin "49") (pinfunction "VSS_49") (pintype "power_in"))
      (node (ref "U3") (pin "74") (pinfunction "VSS_74") (pintype "power_in"))
      (node (ref "U3") (pin "99") (pinfunction "VSS_99") (pintype "power_in"))
      (node (ref "Y2") (pin "2") (pinfunction "2_2") (pintype "passive"))
      (node (ref "Y3") (pin "2") (pinfunction "2_2") (pintype "passive"))
    )
    (net (code "107") (name "Net-(C120-Pad2)") (class "Default")
      (node (ref "C120") (pin "2") (pinfunction "2_2") (pintype "passive"))
      (node (ref "R78") (pin "1") (pinfunction "1_1") (pintype "passive"))
      (node (ref "R81") (pin "2") (pinfunction "2_2") (pintype "passive"))
      (node (ref "Y2") (pin "3") (pinfunction "3_3") (pintype "passive"))
    )
    (net (code "108") (name "Net-(C121-Pad2)") (class "Default")
      (node (ref "C121") (pin "2") (pinfunction "2_2") (pintype "passive"))
      (node (ref "R77") (pin "1") (pinfunction "1_1") (pintype "passive"))
      (node (ref "R82") (pin "2") (pinfunction "2_2") (pintype "passive"))
      (node (ref "Y3") (pin "3") (pinfunction "3_3") (pintype "passive"))
    )
    (net (code "109") (name "Net-(D9-Pad1)") (class "Default")
      (node (ref "D9") (pin "1") (pinfunction "1_1") (pintype "passive"))
      (node (ref "R74") (pin "2") (pinfunction "2_2") (pintype "passive"))
    )
    (net (code "110") (name "Net-(D10-Pad1)") (class "Default")
      (node (ref "D10") (pin "1") (pinfunction "1_1") (pintype "passive"))
      (node (ref "R76") (pin "2") (pinfunction "2_2") (pintype "passive"))
    )
    (net (code "111") (name "Net-(D11-Pad1)") (class "Default")
      (node (ref "D11") (pin "1") (pinfunction "1_1") (pintype "passive"))
      (node (ref "R80") (pin "2") (pinfunction "2_2") (pintype "passive"))
    )
    (net (code "112") (name "Net-(D12-Pad1)") (class "Default")
      (node (ref "D12") (pin "1") (pinfunction "1_1") (pintype "passive"))
      (node (ref "R84") (pin "2") (pinfunction "2_2") (pintype "passive"))
    )
    (net (code "113") (name "Net-(D13-Pad1)") (class "Default")
      (node (ref "D13") (pin "1") (pinfunction "1_1") (pintype "passive"))
      (node (ref "R73") (pin "2") (pinfunction "2_2") (pintype "passive"))
    )
    (net (code "114") (name "Net-(D14-Pad1)") (class "Default")
      (node (ref "D14") (pin "1") (pinfunction "1_1") (pintype "passive"))
      (node (ref "R75") (pin "2") (pinfunction "2_2") (pintype "passive"))
    )
    (net (code "115") (name "Net-(D15-Pad1)") (class "Default")
      (node (ref "D15") (pin "1") (pinfunction "1_1") (pintype "passive"))
      (node (ref "R79") (pin "2") (pinfunction "2_2") (pintype "passive"))
    )
    (net (code "116") (name "Net-(D16-Pad1)") (class "Default")
      (node (ref "D16") (pin "1") (pinfunction "1_1") (pintype "passive"))
      (node (ref "R83") (pin "2") (pinfunction "2_2") (pintype "passive"))
    )
    (net (code "117") (name "Net-(U2-PA13)") (class "Default")
      (node (ref "R101") (pin "1") (pinfunction "1_1") (pintype "passive"))
      (node (ref "U2") (pin "72") (pinfunction "PA13_72") (pintype "bidirectional"))
    )
    (net (code "118") (name "Net-(U2-PA14)") (class "Default")
      (node (ref "R99") (pin "1") (pinfunction "1_1") (pintype "passive"))
      (node (ref "U2") (pin "76") (pinfunction "PA14_76") (pintype "bidirectional"))
    )
    (net (code "119") (name "Net-(U2-PB6)") (class "Default")
      (node (ref "R100") (pin "1") (pinfunction "1_1") (pintype "passive"))
      (node (ref "U2") (pin "92") (pinfunction "PB6_92") (pintype "bidirectional"))
    )
    (net (code "120") (name "Net-(U2-PB7)") (class "Default")
      (node (ref "R96") (pin "1") (pinfunction "1_1") (pintype "passive"))
      (node (ref "U2") (pin "93") (pinfunction "PB7_93") (pintype "bidirectional"))
    )
    (net (code "121") (name "Net-(U2-PB10)") (class "Default")
      (node (ref "R108") (pin "2") (pinfunction "2_2") (pintype "passive"))
      (node (ref "U2") (pin "47") (pinfunction "PB10_47") (pintype "bidirectional"))
    )
    (net (code "122") (name "Net-(U2-PB11)") (class "Default")
      (node (ref "R103") (pin "2") (pinfunction "2_2") (pintype "passive"))
      (node (ref "U2") (pin "48") (pinfunction "PB11_48") (pintype "bidirectional"))
    )
    (net (code "123") (name "Net-(U3-PA13)") (class "Default")
      (node (ref "R102") (pin "1") (pinfunction "1_1") (pintype "passive"))
      (node (ref "U3") (pin "72") (pinfunction "PA13_72") (pintype "bidirectional"))
    )
    (net (code "124") (name "Net-(U3-PA14)") (class "Default")
      (node (ref "R97") (pin "1") (pinfunction "1_1") (pintype "passive"))
      (node (ref "U3") (pin "76") (pinfunction "PA14_76") (pintype "bidirectional"))
    )
    (net (code "125") (name "Net-(U3-PB6)") (class "Default")
      (node (ref "R93") (pin "1") (pinfunction "1_1") (pintype "passive"))
      (node (ref "U3") (pin "92") (pinfunction "PB6_92") (pintype "bidirectional"))
    )
    (net (code "126") (name "Net-(U3-PB7)") (class "Default")
      (node (ref "R98") (pin "1") (pinfunction "1_1") (pintype "passive"))
      (node (ref "U3") (pin "93") (pinfunction "PB7_93") (pintype "bidirectional"))
    )
    (net (code "127") (name "Net-(U3-PB10)") (class "Default")
      (node (ref "R104") (pin "2") (pinfunction "2_2") (pintype "passive"))
      (node (ref "U3") (pin "47") (pinfunction "PB10_47") (pintype "bidirectional"))
    )
    (net (code "128") (name "Net-(U3-PB11)") (class "Default")
      (node (ref "R105") (pin "2") (pinfunction "2_2") (pintype "passive"))
      (node (ref "U3") (pin "48") (pinfunction "PB11_48") (pintype "bidirectional"))
    )
    (net (code "129") (name "unconnected-(U2-BOOT0-Pad94)") (class "Default")
      (node (ref "U2") (pin "94") (pinfunction "BOOT0_94") (pintype "input+no_connect"))
    )
    (net (code "130") (name "unconnected-(U2-NC-Pad73)") (class "Default")
      (node (ref "U2") (pin "73") (pinfunction "NC_73") (pintype "bidirectional+no_connect"))
    )
    (net (code "131") (name "unconnected-(U2-NRST-Pad14)") (class "Default")
      (node (ref "U2") (pin "14") (pinfunction "NRST_14") (pintype "bidirectional+no_connect"))
    )
    (net (code "132") (name "unconnected-(U2-PA12-Pad71)") (class "Default")
      (node (ref "U2") (pin "71") (pinfunction "PA12_71") (pintype "bidirectional+no_connect"))
    )
    (net (code "133") (name "unconnected-(U2-PA15-Pad77)") (class "Default")
      (node (ref "U2") (pin "77") (pinfunction "PA15_77") (pintype "bidirectional+no_connect"))
    )
    (net (code "134") (name "unconnected-(U2-PB5-Pad91)") (class "Default")
      (node (ref "U2") (pin "91") (pinfunction "PB5_91") (pintype "bidirectional+no_connect"))
    )
    (net (code "135") (name "unconnected-(U2-PC0-Pad15)") (class "Default")
      (node (ref "U2") (pin "15") (pinfunction "PC0_15") (pintype "bidirectional+no_connect"))
    )
    (net (code "136") (name "unconnected-(U2-PC1-Pad16)") (class "Default")
      (node (ref "U2") (pin "16") (pinfunction "PC1_16") (pintype "bidirectional+no_connect"))
    )
    (net (code "137") (name "unconnected-(U2-PC2-Pad17)") (class "Default")
      (node (ref "U2") (pin "17") (pinfunction "PC2_17") (pintype "bidirectional+no_connect"))
    )
    (net (code "138") (name "unconnected-(U2-PC3-Pad18)") (class "Default")
      (node (ref "U2") (pin "18") (pinfunction "PC3_18") (pintype "bidirectional+no_connect"))
    )
    (net (code "139") (name "unconnected-(U2-PC10-Pad78)") (class "Default")
      (node (ref "U2") (pin "78") (pinfunction "PC10_78") (pintype "bidirectional+no_connect"))
    )
    (net (code "140") (name "unconnected-(U2-PC11-Pad79)") (class "Default")
      (node (ref "U2") (pin "79") (pinfunction "PC11_79") (pintype "bidirectional+no_connect"))
    )
    (net (code "141") (name "unconnected-(U2-PC12-Pad80)") (class "Default")
      (node (ref "U2") (pin "80") (pinfunction "PC12_80") (pintype "bidirectional+no_connect"))
    )
    (net (code "142") (name "unconnected-(U2-PC13-TAMPER-RTC-Pad7)") (class "Default")
      (node (ref "U2") (pin "7") (pinfunction "PC13-TAMPER-RTC_7") (pintype "bidirectional+no_connect"))
    )
    (net (code "143") (name "unconnected-(U2-PC14-OSC32_IN-Pad8)") (class "Default")
      (node (ref "U2") (pin "8") (pinfunction "PC14-OSC32_IN_8") (pintype "bidirectional+no_connect"))
    )
    (net (code "144") (name "unconnected-(U2-PC15-OSC32_OUT-Pad9)") (class "Default")
      (node (ref "U2") (pin "9") (pinfunction "PC15-OSC32_OUT_9") (pintype "bidirectional+no_connect"))
    )
    (net (code "145") (name "unconnected-(U2-PD0-Pad81)") (class "Default")
      (node (ref "U2") (pin "81") (pinfunction "PD0_81") (pintype "bidirectional+no_connect"))
    )
    (net (code "146") (name "unconnected-(U2-PD1-Pad82)") (class "Default")
      (node (ref "U2") (pin "82") (pinfunction "PD1_82") (pintype "bidirectional+no_connect"))
    )
    (net (code "147") (name "unconnected-(U2-PD2-Pad83)") (class "Default")
      (node (ref "U2") (pin "83") (pinfunction "PD2_83") (pintype "bidirectional+no_connect"))
    )
    (net (code "148") (name "unconnected-(U2-PD3-Pad84)") (class "Default")
      (node (ref "U2") (pin "84") (pinfunction "PD3_84") (pintype "bidirectional+no_connect"))
    )
    (net (code "149") (name "unconnected-(U2-PD4-Pad85)") (class "Default")
      (node (ref "U2") (pin "85") (pinfunction "PD4_85") (pintype "bidirectional+no_connect"))
    )
    (net (code "150") (name "unconnected-(U2-PD5-Pad86)") (class "Default")
      (node (ref "U2") (pin "86") (pinfunction "PD5_86") (pintype "bidirectional+no_connect"))
    )
    (net (code "151") (name "unconnected-(U2-PE0-Pad97)") (class "Default")
      (node (ref "U2") (pin "97") (pinfunction "PE0_97") (pintype "bidirectional+no_connect"))
    )
    (net (code "152") (name "unconnected-(U2-PE1-Pad98)") (class "Default")
      (node (ref "U2") (pin "98") (pinfunction "PE1_98") (pintype "power_in+no_connect"))
    )
    (net (code "153") (name "unconnected-(U2-PE2-Pad1)") (class "Default")
      (node (ref "U2") (pin "1") (pinfunction "PE2_1") (pintype "bidirectional+no_connect"))
    )
    (net (code "154") (name "unconnected-(U2-PE3-Pad2)") (class "Default")
      (node (ref "U2") (pin "2") (pinfunction "PE3_2") (pintype "bidirectional+no_connect"))
    )
    (net (code "155") (name "unconnected-(U2-PE4-Pad3)") (class "Default")
      (node (ref "U2") (pin "3") (pinfunction "PE4_3") (pintype "bidirectional+no_connect"))
    )
    (net (code "156") (name "unconnected-(U2-PE5-Pad4)") (class "Default")
      (node (ref "U2") (pin "4") (pinfunction "PE5_4") (pintype "bidirectional+no_connect"))
    )
    (net (code "157") (name "unconnected-(U2-PE6-Pad5)") (class "Default")
      (node (ref "U2") (pin "5") (pinfunction "PE6_5") (pintype "bidirectional+no_connect"))
    )
    (net (code "158") (name "unconnected-(U2-PE8-Pad39)") (class "Default")
      (node (ref "U2") (pin "39") (pinfunction "PE8_39") (pintype "bidirectional+no_connect"))
    )
    (net (code "159") (name "unconnected-(U2-PE10-Pad41)") (class "Default")
      (node (ref "U2") (pin "41") (pinfunction "PE10_41") (pintype "bidirectional+no_connect"))
    )
    (net (code "160") (name "unconnected-(U2-PE12-Pad43)") (class "Default")
      (node (ref "U2") (pin "43") (pinfunction "PE12_43") (pintype "bidirectional+no_connect"))
    )
    (net (code "161") (name "unconnected-(U2-PE13-Pad44)") (class "Default")
      (node (ref "U2") (pin "44") (pinfunction "PE13_44") (pintype "bidirectional+no_connect"))
    )
    (net (code "162") (name "unconnected-(U2-PE14-Pad45)") (class "Default")
      (node (ref "U2") (pin "45") (pinfunction "PE14_45") (pintype "bidirectional+no_connect"))
    )
    (net (code "163") (name "unconnected-(U2-PE15-Pad46)") (class "Default")
      (node (ref "U2") (pin "46") (pinfunction "PE15_46") (pintype "bidirectional+no_connect"))
    )
    (net (code "164") (name "unconnected-(U3-BOOT0-Pad94)") (class "Default")
      (node (ref "U3") (pin "94") (pinfunction "BOOT0_94") (pintype "input+no_connect"))
    )
    (net (code "165") (name "unconnected-(U3-NC-Pad73)") (class "Default")
      (node (ref "U3") (pin "73") (pinfunction "NC_73") (pintype "bidirectional+no_connect"))
    )
    (net (code "166") (name "unconnected-(U3-NRST-Pad14)") (class "Default")
      (node (ref "U3") (pin "14") (pinfunction "NRST_14") (pintype "bidirectional+no_connect"))
    )
    (net (code "167") (name "unconnected-(U3-PA12-Pad71)") (class "Default")
      (node (ref "U3") (pin "71") (pinfunction "PA12_71") (pintype "bidirectional+no_connect"))
    )
    (net (code "168") (name "unconnected-(U3-PA15-Pad77)") (class "Default")
      (node (ref "U3") (pin "77") (pinfunction "PA15_77") (pintype "bidirectional+no_connect"))
    )
    (net (code "169") (name "unconnected-(U3-PB5-Pad91)") (class "Default")
      (node (ref "U3") (pin "91") (pinfunction "PB5_91") (pintype "bidirectional+no_connect"))
    )
    (net (code "170") (name "unconnected-(U3-PC0-Pad15)") (class "Default")
      (node (ref "U3") (pin "15") (pinfunction "PC0_15") (pintype "bidirectional+no_connect"))
    )
    (net (code "171") (name "unconnected-(U3-PC1-Pad16)") (class "Default")
      (node (ref "U3") (pin "16") (pinfunction "PC1_16") (pintype "bidirectional+no_connect"))
    )
    (net (code "172") (name "unconnected-(U3-PC2-Pad17)") (class "Default")
      (node (ref "U3") (pin "17") (pinfunction "PC2_17") (pintype "bidirectional+no_connect"))
    )
    (net (code "173") (name "unconnected-(U3-PC3-Pad18)") (class "Default")
      (node (ref "U3") (pin "18") (pinfunction "PC3_18") (pintype "bidirectional+no_connect"))
    )
    (net (code "174") (name "unconnected-(U3-PC10-Pad78)") (class "Default")
      (node (ref "U3") (pin "78") (pinfunction "PC10_78") (pintype "bidirectional+no_connect"))
    )
    (net (code "175") (name "unconnected-(U3-PC11-Pad79)") (class "Default")
      (node (ref "U3") (pin "79") (pinfunction "PC11_79") (pintype "bidirectional+no_connect"))
    )
    (net (code "176") (name "unconnected-(U3-PC12-Pad80)") (class "Default")
      (node (ref "U3") (pin "80") (pinfunction "PC12_80") (pintype "bidirectional+no_connect"))
    )
    (net (code "177") (name "unconnected-(U3-PC13-TAMPER-RTC-Pad7)") (class "Default")
      (node (ref "U3") (pin "7") (pinfunction "PC13-TAMPER-RTC_7") (pintype "bidirectional+no_connect"))
    )
    (net (code "178") (name "unconnected-(U3-PC14-OSC32_IN-Pad8)") (class "Default")
      (node (ref "U3") (pin "8") (pinfunction "PC14-OSC32_IN_8") (pintype "bidirectional+no_connect"))
    )
    (net (code "179") (name "unconnected-(U3-PC15-OSC32_OUT-Pad9)") (class "Default")
      (node (ref "U3") (pin "9") (pinfunction "PC15-OSC32_OUT_9") (pintype "bidirectional+no_connect"))
    )
    (net (code "180") (name "unconnected-(U3-PD0-Pad81)") (class "Default")
      (node (ref "U3") (pin "81") (pinfunction "PD0_81") (pintype "bidirectional+no_connect"))
    )
    (net (code "181") (name "unconnected-(U3-PD1-Pad82)") (class "Default")
      (node (ref "U3") (pin "82") (pinfunction "PD1_82") (pintype "bidirectional+no_connect"))
    )
    (net (code "182") (name "unconnected-(U3-PD2-Pad83)") (class "Default")
      (node (ref "U3") (pin "83") (pinfunction "PD2_83") (pintype "bidirectional+no_connect"))
    )
    (net (code "183") (name "unconnected-(U3-PD3-Pad84)") (class "Default")
      (node (ref "U3") (pin "84") (pinfunction "PD3_84") (pintype "bidirectional+no_connect"))
    )
    (net (code "184") (name "unconnected-(U3-PD4-Pad85)") (class "Default")
      (node (ref "U3") (pin "85") (pinfunction "PD4_85") (pintype "bidirectional+no_connect"))
    )
    (net (code "185") (name "unconnected-(U3-PD5-Pad86)") (class "Default")
      (node (ref "U3") (pin "86") (pinfunction "PD5_86") (pintype "bidirectional+no_connect"))
    )
    (net (code "186") (name "unconnected-(U3-PE0-Pad97)") (class "Default")
      (node (ref "U3") (pin "97") (pinfunction "PE0_97") (pintype "bidirectional+no_connect"))
    )
    (net (code "187") (name "unconnected-(U3-PE1-Pad98)") (class "Default")
      (node (ref "U3") (pin "98") (pinfunction "PE1_98") (pintype "power_in+no_connect"))
    )
    (net (code "188") (name "unconnected-(U3-PE2-Pad1)") (class "Default")
      (node (ref "U3") (pin "1") (pinfunction "PE2_1") (pintype "bidirectional+no_connect"))
    )
    (net (code "189") (name "unconnected-(U3-PE3-Pad2)") (class "Default")
      (node (ref "U3") (pin "2") (pinfunction "PE3_2") (pintype "bidirectional+no_connect"))
    )
    (net (code "190") (name "unconnected-(U3-PE4-Pad3)") (class "Default")
      (node (ref "U3") (pin "3") (pinfunction "PE4_3") (pintype "bidirectional+no_connect"))
    )
    (net (code "191") (name "unconnected-(U3-PE5-Pad4)") (class "Default")
      (node (ref "U3") (pin "4") (pinfunction "PE5_4") (pintype "bidirectional+no_connect"))
    )
    (net (code "192") (name "unconnected-(U3-PE6-Pad5)") (class "Default")
      (node (ref "U3") (pin "5") (pinfunction "PE6_5") (pintype "bidirectional+no_connect"))
    )
    (net (code "193") (name "unconnected-(U3-PE8-Pad39)") (class "Default")
      (node (ref "U3") (pin "39") (pinfunction "PE8_39") (pintype "bidirectional+no_connect"))
    )
    (net (code "194") (name "unconnected-(U3-PE10-Pad41)") (class "Default")
      (node (ref "U3") (pin "41") (pinfunction "PE10_41") (pintype "bidirectional+no_connect"))
    )
    (net (code "195") (name "unconnected-(U3-PE12-Pad43)") (class "Default")
      (node (ref "U3") (pin "43") (pinfunction "PE12_43") (pintype "bidirectional+no_connect"))
    )
    (net (code "196") (name "unconnected-(U3-PE13-Pad44)") (class "Default")
      (node (ref "U3") (pin "44") (pinfunction "PE13_44") (pintype "bidirectional+no_connect"))
    )
    (net (code "197") (name "unconnected-(U3-PE14-Pad45)") (class "Default")
      (node (ref "U3") (pin "45") (pinfunction "PE14_45") (pintype "bidirectional+no_connect"))
    )
    (net (code "198") (name "unconnected-(U3-PE15-Pad46)") (class "Default")
      (node (ref "U3") (pin "46") (pinfunction "PE15_46") (pintype "bidirectional+no_connect"))
    )
  )
)
